# Top.net
KiCad netlist of a schematic drawn in Altium Designer
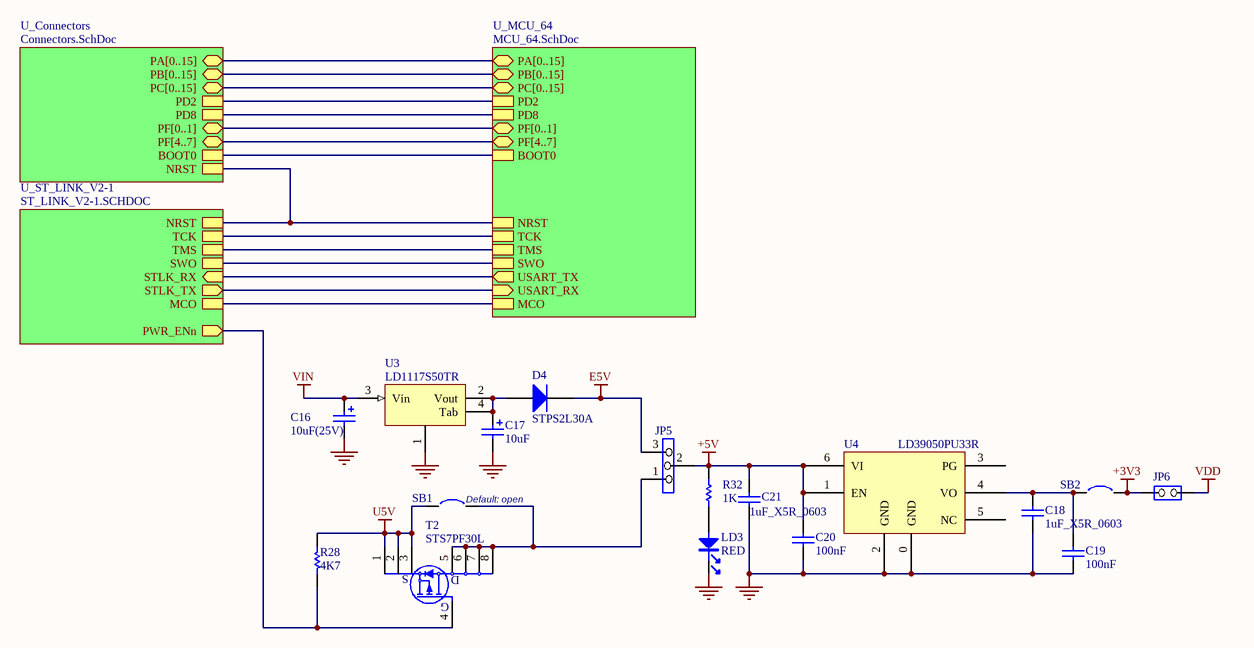
[diagram p0: Top.SchDoc]

(export (version "E")
  (design (tool "Eeschema 10.0.6"))
  (components
    (comp (ref "C16")
      (value "10uF(25V)")
      (footprint "TAN-B")
      (description "Polarized Capacitor (Radial)")
      (fields (field (name "PUBLISHER") "Altium Limited"))
      (libsource (lib "Miscellaneous Devices") (part "Cap Pol1"))
    )
    (comp (ref "C17")
      (value "10uF")
      (footprint "TAN-A")
      (description "Polarized Capacitor (Radial)")
      (fields (field (name "PUBLISHER") "Altium Limited"))
      (libsource (lib "Miscellaneous Devices") (part "Cap Pol1"))
    )
    (comp (ref "C18")
      (value "1uF_X5R_0603")
      (footprint "0603C")
      (description "0603  X5R 1µF")
      (fields (field (name "TOLERANCE") "10%"))
      (libsource (lib "MB963_1") (part "CAP SMD 0603  X5R 1µF 25V 10%"))
    )
    (comp (ref "C19")
      (value "100nF")
      (footprint "0603C")
      (description "Capacitor 0402 / 0603 / 0805")
      (libsource (lib "MCD_TOOLS") (part "Capacitor_ST"))
    )
    (comp (ref "C20")
      (value "100nF")
      (footprint "0603C")
      (description "Capacitor 0402 / 0603 / 0805")
      (libsource (lib "MCD_TOOLS") (part "Capacitor_ST"))
    )
    (comp (ref "C21")
      (value "1uF_X5R_0603")
      (footprint "0603C")
      (description "0603  X5R 1µF")
      (fields (field (name "TOLERANCE") "10%"))
      (libsource (lib "MB963_1") (part "CAP SMD 0603  X5R 1µF 25V 10%"))
    )
    (comp (ref "D4") (value "STPS2L30A") (footprint "SMA") (libsource (lib "Nucleo_64") (part "STPS2L30A")))
    (comp (ref "JP5") (value "~") (footprint "SIP3") (libsource (lib "STR910_SCHLIB") (part "Jumper3")))
    (comp (ref "JP6") (value "~") (footprint "SIP2/2.54") (libsource (lib "*") (part "JP2")))
    (comp (ref "LD3") (value "RED") (footprint "0603D") (libsource (lib "MB963_1") (part "PHOTO")))
    (comp (ref "R28")
      (value "4K7")
      (footprint "0603R")
      (description "Resistor")
      (fields (field (name "PUBLISHER") "Altium Limited"))
      (libsource (lib "*") (part "Res1"))
    )
    (comp (ref "R32")
      (value "1K")
      (footprint "0603R")
      (description "Resistor 0402 / 0603 / 0805")
      (libsource (lib "MCD_TOOLS") (part "Resistor_ST"))
    )
    (comp (ref "SB1")
      (value "Circuit Breaker")
      (footprint "JP2_SMD")
      (fields (field (name "PUBLISHER") "Altium Limited"))
      (libsource (lib "MCD_TOOLS") (part "Circuit Breaker"))
    )
    (comp (ref "SB2")
      (value "Circuit Breaker")
      (footprint "JP2_SMD")
      (fields (field (name "PUBLISHER") "Altium Limited"))
      (libsource (lib "MCD_TOOLS") (part "Circuit Breaker"))
    )
    (comp (ref "T2") (value "STS7PF30L") (footprint "SO8") (libsource (lib "Nucleo_64") (part "STS7PF30L")))
    (comp (ref "U3") (value "LD1117S50TR") (footprint "SOT-223") (libsource (lib "mb1045") (part "LD1117")))
    (comp (ref "U4")
      (value "LD39050PU33R")
      (footprint "DFN6(3X3)")
      (libsource (lib "Nucleo_64") (part "LD39050P"))
    )
  )
  (nets
    (net (code "1") (name "+3V3") (class "Default")
      (node (ref "JP6") (pin "1") (pinfunction "COMMON_1") (pintype "passive"))
      (node (ref "SB2") (pin "2") (pinfunction "2_2") (pintype "passive"))
    )
    (net (code "2") (name "+5V") (class "Default")
      (node (ref "C20") (pin "2") (pinfunction "2_2") (pintype "passive"))
      (node (ref "C21") (pin "1") (pinfunction "1_1") (pintype "passive"))
      (node (ref "JP5") (pin "2") (pintype "passive"))
      (node (ref "R32") (pin "2") (pinfunction "2_2") (pintype "passive"))
      (node (ref "U4") (pin "1") (pinfunction "EN_1") (pintype "passive"))
      (node (ref "U4") (pin "6") (pinfunction "VI_6") (pintype "passive"))
    )
    (net (code "13") (name "/PWR_ENn") (class "Default")
      (node (ref "R28") (pin "2") (pinfunction "2_2") (pintype "passive"))
      (node (ref "T2") (pin "4") (pinfunction "G_4") (pintype "passive"))
    )
    (net (code "19") (name "E5V") (class "Default")
      (node (ref "D4") (pin "2") (pinfunction "K_2") (pintype "passive"))
      (node (ref "JP5") (pin "3") (pintype "passive"))
    )
    (net (code "20") (name "GND") (class "Default")
      (node (ref "C16") (pin "2") (pinfunction "2_2") (pintype "passive"))
      (node (ref "C17") (pin "2") (pinfunction "2_2") (pintype "passive"))
      (node (ref "C18") (pin "2") (pinfunction "2_2") (pintype "passive"))
      (node (ref "C19") (pin "1") (pinfunction "1_1") (pintype "passive"))
      (node (ref "C20") (pin "1") (pinfunction "1_1") (pintype "passive"))
      (node (ref "C21") (pin "2") (pinfunction "2_2") (pintype "passive"))
      (node (ref "LD3") (pin "2") (pintype "passive"))
      (node (ref "U3") (pin "1") (pintype "passive"))
      (node (ref "U4") (pin "0") (pinfunction "GND_0") (pintype "passive"))
      (node (ref "U4") (pin "2") (pinfunction "GND_2") (pintype "passive"))
    )
    (net (code "21") (name "Net-(D4-A)") (class "Default")
      (node (ref "C17") (pin "1") (pinfunction "1_1") (pintype "passive"))
      (node (ref "D4") (pin "1") (pinfunction "A_1") (pintype "passive"))
      (node (ref "U3") (pin "2") (pinfunction "Vout_2") (pintype "power_in"))
      (node (ref "U3") (pin "4") (pinfunction "Tab_4") (pintype "power_in"))
    )
    (net (code "22") (name "Net-(JP5-Pad1)") (class "Default")
      (node (ref "JP5") (pin "1") (pintype "passive"))
      (node (ref "SB1") (pin "2") (pinfunction "2_2") (pintype "passive"))
      (node (ref "T2") (pin "5") (pinfunction "D_5") (pintype "passive"))
      (node (ref "T2") (pin "6") (pinfunction "D_6") (pintype "passive"))
      (node (ref "T2") (pin "7") (pinfunction "D_7") (pintype "passive"))
      (node (ref "T2") (pin "8") (pinfunction "D_8") (pintype "passive"))
    )
    (net (code "23") (name "Net-(LD3-Pad1)") (class "Default")
      (node (ref "LD3") (pin "1") (pintype "passive"))
      (node (ref "R32") (pin "1") (pinfunction "1_1") (pintype "passive"))
    )
    (net (code "24") (name "Net-(U4-VO)") (class "Default")
      (node (ref "C18") (pin "1") (pinfunction "1_1") (pintype "passive"))
      (node (ref "C19") (pin "2") (pinfunction "2_2") (pintype "passive"))
      (node (ref "SB2") (pin "1") (pinfunction "1_1") (pintype "passive"))
      (node (ref "U4") (pin "4") (pinfunction "VO_4") (pintype "passive"))
    )
    (net (code "25") (name "U5V") (class "Default")
      (node (ref "R28") (pin "1") (pinfunction "1_1") (pintype "passive"))
      (node (ref "SB1") (pin "1") (pinfunction "1_1") (pintype "passive"))
      (node (ref "T2") (pin "1") (pinfunction "S_1") (pintype "passive"))
      (node (ref "T2") (pin "2") (pinfunction "S_2") (pintype "passive"))
      (node (ref "T2") (pin "3") (pinfunction "S_3") (pintype "passive"))
    )
    (net (code "26") (name "VDD") (class "Default")
      (node (ref "JP6") (pin "2") (pinfunction "NO_2") (pintype "passive"))
    )
    (net (code "27") (name "VIN") (class "Default")
      (node (ref "C16") (pin "1") (pinfunction "1_1") (pintype "passive"))
      (node (ref "U3") (pin "3") (pinfunction "Vin_3") (pintype "input"))
    )
    (net (code "28") (name "unconnected-(U4-NC-Pad5)") (class "Default")
      (node (ref "U4") (pin "5") (pinfunction "NC_5") (pintype "passive"))
    )
    (net (code "29") (name "unconnected-(U4-PG-Pad3)") (class "Default")
      (node (ref "U4") (pin "3") (pinfunction "PG_3") (pintype "passive"))
    )
  )
)
